# PCB_MASTER_CARRO_MYM.net
KiCad netlist of a schematic drawn in EAGLE
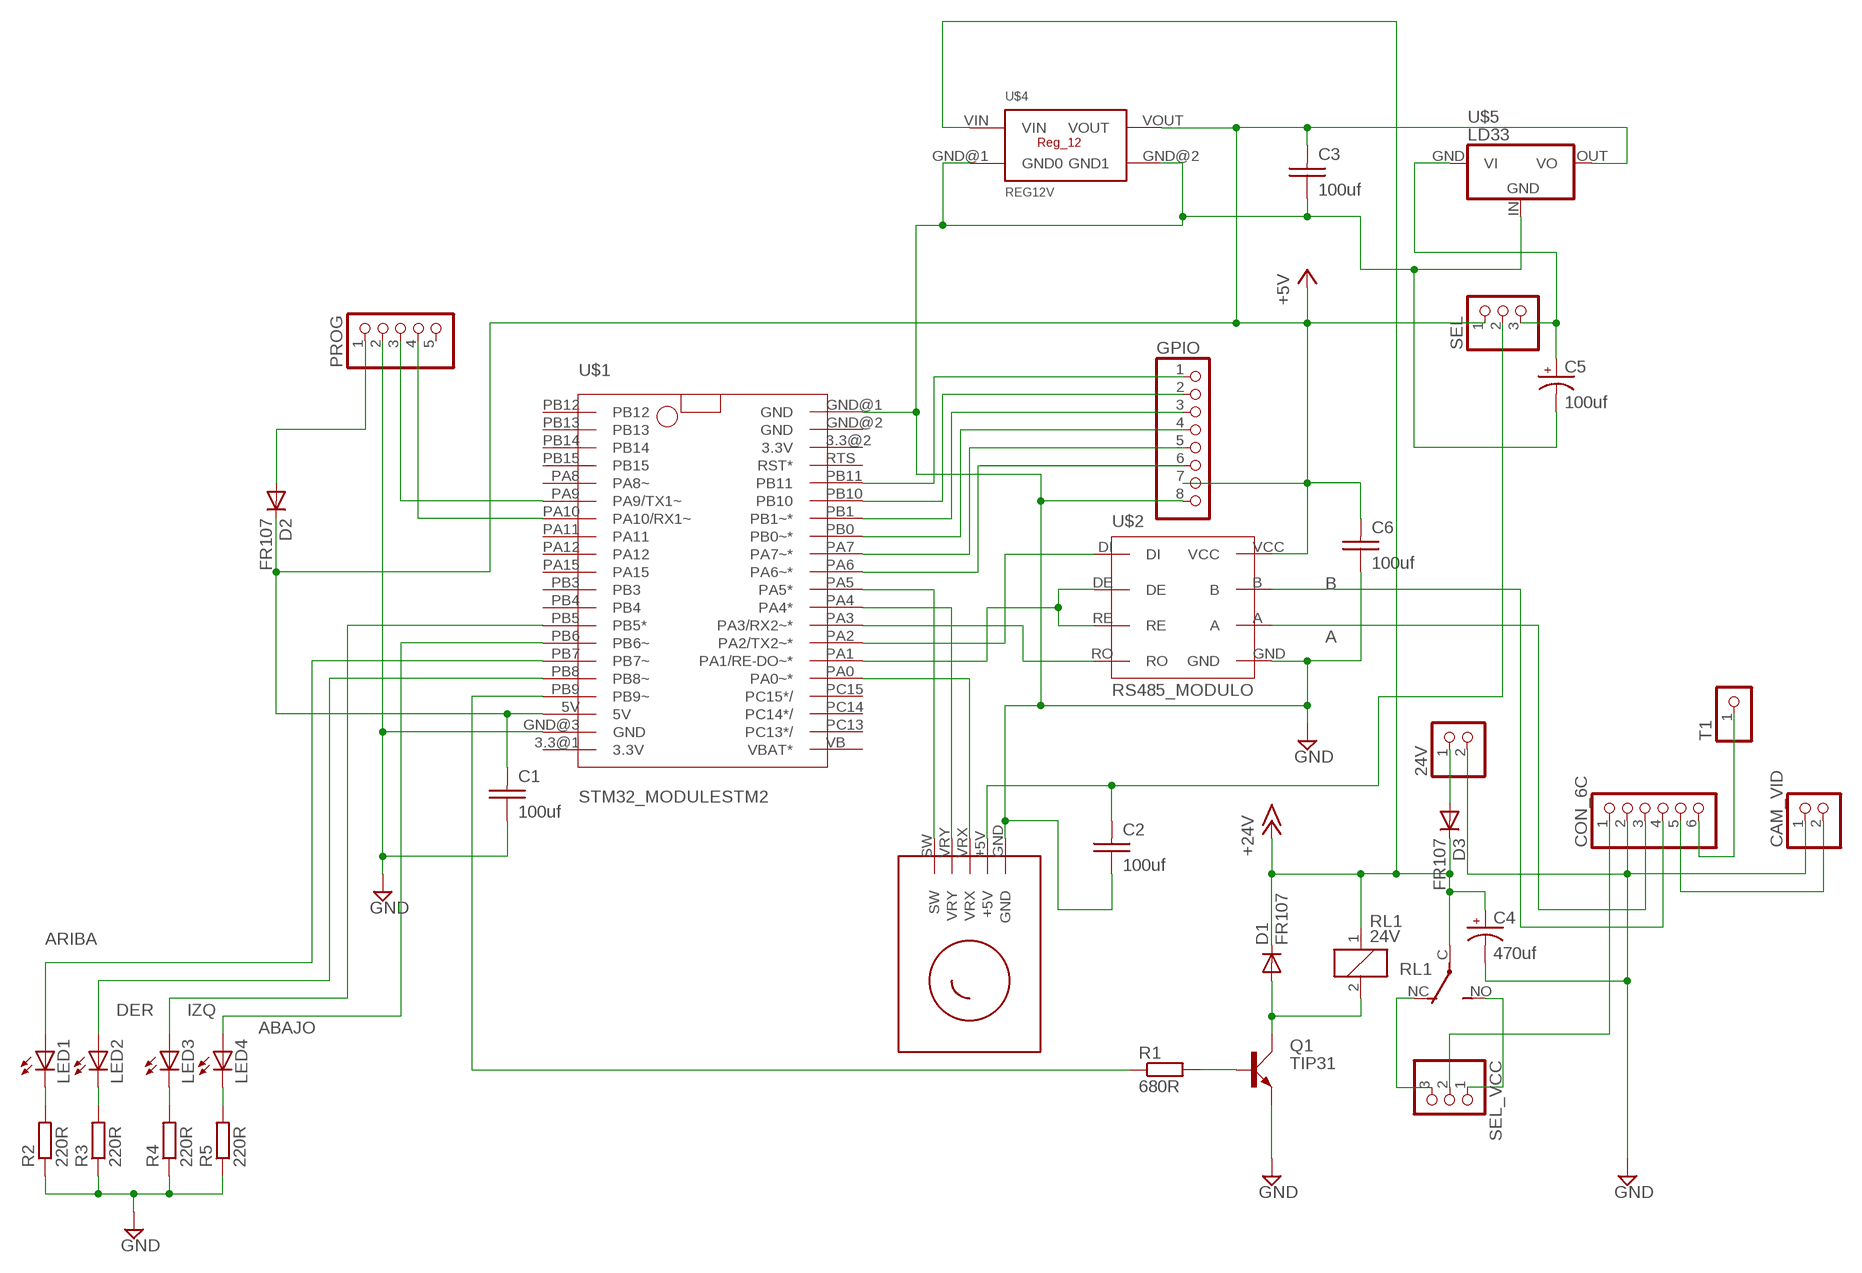
[diagram p0: schematic, sheet 1]

(export (version "E")
  (design (tool "Eeschema 10.0.6"))
  (components
    (comp (ref "24V")
      (value "PINHD-1X2")
      (footprint "eagle-import:1X02")
      (libsource (lib "eagle-import") (part "PINHD-1X2"))
    )
    (comp (ref "C1")
      (value "100uf")
      (footprint "eagle-import:CAP_CER_2,54-5X5")
      (libsource (lib "eagle-import") (part "CAP_CERAMICO_TH2"))
    )
    (comp (ref "C2")
      (value "100uf")
      (footprint "eagle-import:CAP_CER_2,54-5X5")
      (libsource (lib "eagle-import") (part "CAP_CERAMICO_TH2"))
    )
    (comp (ref "C3")
      (value "100uf")
      (footprint "eagle-import:CAP_CER_2,54-5X5")
      (libsource (lib "eagle-import") (part "CAP_CERAMICO_TH2"))
    )
    (comp (ref "C4")
      (value "470uf")
      (footprint "eagle-import:CAP_T_5-D8,5")
      (libsource (lib "eagle-import") (part "CAP_POLARIZADOCAP_T5-8,5"))
    )
    (comp (ref "C5")
      (value "100uf")
      (footprint "eagle-import:CAP_T_3,5-D8")
      (libsource (lib "eagle-import") (part "CAP_POLARIZADOCAP_T3,5-D8"))
    )
    (comp (ref "C6")
      (value "100uf")
      (footprint "eagle-import:CAP_CER_2,54-5X5")
      (libsource (lib "eagle-import") (part "CAP_CERAMICO_TH2"))
    )
    (comp (ref "CAM_VID")
      (value "PINHD-1X2")
      (footprint "eagle-import:1X02")
      (libsource (lib "eagle-import") (part "PINHD-1X2"))
    )
    (comp (ref "CON_6C")
      (value "PINHD-1X6")
      (footprint "eagle-import:1X06")
      (libsource (lib "eagle-import") (part "PINHD-1X6"))
    )
    (comp (ref "D1")
      (value "FR107")
      (footprint "eagle-import:D-5")
      (libsource (lib "eagle-import") (part "DIODOT_5"))
    )
    (comp (ref "D2")
      (value "FR107")
      (footprint "eagle-import:DIODO4MM")
      (libsource (lib "eagle-import") (part "DIODO"))
    )
    (comp (ref "D3")
      (value "FR107")
      (footprint "eagle-import:DIODO4MM")
      (libsource (lib "eagle-import") (part "DIODO"))
    )
    (comp (ref "GPIO")
      (value "PINHD-1X8")
      (footprint "eagle-import:1X08")
      (libsource (lib "eagle-import") (part "PINHD-1X8"))
    )
    (comp (ref "LED1")
      (value "LEDLED_T_3MM")
      (footprint "eagle-import:LED3MM")
      (libsource (lib "eagle-import") (part "LEDLED_T_3MM"))
    )
    (comp (ref "LED2")
      (value "LEDLED_T_3MM")
      (footprint "eagle-import:LED3MM")
      (libsource (lib "eagle-import") (part "LEDLED_T_3MM"))
    )
    (comp (ref "LED3")
      (value "LEDLED_T_3MM")
      (footprint "eagle-import:LED3MM")
      (libsource (lib "eagle-import") (part "LEDLED_T_3MM"))
    )
    (comp (ref "LED4")
      (value "LEDLED_T_3MM")
      (footprint "eagle-import:LED3MM")
      (libsource (lib "eagle-import") (part "LEDLED_T_3MM"))
    )
    (comp (ref "PROG")
      (value "PINHD-1X5")
      (footprint "eagle-import:1X05")
      (libsource (lib "eagle-import") (part "PINHD-1X5"))
    )
    (comp (ref "Q1")
      (value "TIP31")
      (footprint "eagle-import:TO220")
      (libsource (lib "eagle-import") (part "TIP48_TH"))
    )
    (comp (ref "R1")
      (value "680R")
      (footprint "eagle-import:0204_5")
      (libsource (lib "eagle-import") (part "RESISTORT_LARGO"))
    )
    (comp (ref "R2")
      (value "220R")
      (footprint "eagle-import:0204_5")
      (libsource (lib "eagle-import") (part "RESISTORT_LARGO"))
    )
    (comp (ref "R3")
      (value "220R")
      (footprint "eagle-import:0204_5")
      (libsource (lib "eagle-import") (part "RESISTORT_LARGO"))
    )
    (comp (ref "R4")
      (value "220R")
      (footprint "eagle-import:0204_5")
      (libsource (lib "eagle-import") (part "RESISTORT_LARGO"))
    )
    (comp (ref "R5")
      (value "220R")
      (footprint "eagle-import:0204_5")
      (libsource (lib "eagle-import") (part "RESISTORT_LARGO"))
    )
    (comp (ref "RL1")
      (value "24V")
      (footprint "eagle-import:CQ1")
      (libsource (lib "eagle-import") (part "CQ1-12V"))
    )
    (comp (ref "SEL")
      (value "PINHD-1X3")
      (footprint "eagle-import:1X03")
      (libsource (lib "eagle-import") (part "PINHD-1X3"))
    )
    (comp (ref "SEL_VCC")
      (value "PINHD-1X3")
      (footprint "eagle-import:1X03")
      (libsource (lib "eagle-import") (part "PINHD-1X3"))
    )
    (comp (ref "T1")
      (value "PINHD-1X1")
      (footprint "eagle-import:1X01")
      (libsource (lib "eagle-import") (part "PINHD-1X1"))
    )
    (comp (ref "U$1")
      (value "STM32_MODULESTM2")
      (footprint "eagle-import:STM_32MOD")
      (libsource (lib "eagle-import") (part "STM32_MODULESTM2"))
    )
    (comp (ref "U$2")
      (value "RS485_MODULO")
      (footprint "eagle-import:RS485_FP")
      (libsource (lib "eagle-import") (part "RS485_MODULO"))
    )
    (comp (ref "U$3")
      (value "JOYSTICK")
      (footprint "eagle-import:JOYSTICK")
      (libsource (lib "eagle-import") (part "JOYSTICK"))
    )
    (comp (ref "U$4")
      (value "REG12V")
      (footprint "eagle-import:REG12V")
      (libsource (lib "eagle-import") (part "REG12V"))
    )
    (comp (ref "U$5")
      (value "LD33")
      (footprint "eagle-import:78XXS")
      (libsource (lib "eagle-import") (part "LD33"))
    )
  )
  (nets
    (net (code "1") (name "+5V") (class "Default")
      (node (ref "C1") (pin "1") (pinfunction "1_1") (pintype "passive"))
      (node (ref "C3") (pin "1") (pinfunction "1_1") (pintype "passive"))
      (node (ref "C6") (pin "1") (pinfunction "1_1") (pintype "passive"))
      (node (ref "D2") (pin "C") (pinfunction "C_C") (pintype "passive"))
      (node (ref "GPIO") (pin "7") (pinfunction "7_7") (pintype "passive"))
      (node (ref "SEL") (pin "1") (pinfunction "1_1") (pintype "passive"))
      (node (ref "U$1") (pin "5V") (pinfunction "5V_5V") (pintype "bidirectional"))
      (node (ref "U$2") (pin "VCC") (pinfunction "VCC_VCC") (pintype "bidirectional"))
      (node (ref "U$4") (pin "VOUT") (pinfunction "VOUT_VOUT") (pintype "bidirectional"))
      (node (ref "U$5") (pin "OUT") (pinfunction "VO_OUT") (pintype "passive"))
    )
    (net (code "2") (name "+24V") (class "Default")
      (node (ref "C4") (pin "+") (pinfunction "+_+") (pintype "passive"))
      (node (ref "D1") (pin "C") (pinfunction "C_C") (pintype "passive"))
      (node (ref "D3") (pin "C") (pinfunction "C_C") (pintype "passive"))
      (node (ref "RL1") (pin "1") (pinfunction "1_1") (pintype "passive"))
      (node (ref "RL1") (pin "C") (pinfunction "P_C") (pintype "passive"))
      (node (ref "U$4") (pin "VIN") (pinfunction "VIN_VIN") (pintype "bidirectional"))
    )
    (net (code "3") (name "/A") (class "Default")
      (node (ref "CON_6C") (pin "3") (pinfunction "3_3") (pintype "passive"))
      (node (ref "U$2") (pin "A") (pinfunction "A_A") (pintype "bidirectional"))
    )
    (net (code "4") (name "/ABAJO") (class "Default")
      (node (ref "LED4") (pin "A") (pinfunction "A_A") (pintype "passive"))
      (node (ref "U$1") (pin "PB6") (pinfunction "PB6~{}_PB6") (pintype "bidirectional"))
    )
    (net (code "5") (name "/ARIBA") (class "Default")
      (node (ref "LED1") (pin "A") (pinfunction "A_A") (pintype "passive"))
      (node (ref "U$1") (pin "PB7") (pinfunction "PB7~{}_PB7") (pintype "bidirectional"))
    )
    (net (code "6") (name "/B") (class "Default")
      (node (ref "CON_6C") (pin "4") (pinfunction "4_4") (pintype "passive"))
      (node (ref "U$2") (pin "B") (pinfunction "B_B") (pintype "bidirectional"))
    )
    (net (code "7") (name "/DER") (class "Default")
      (node (ref "LED2") (pin "A") (pinfunction "A_A") (pintype "passive"))
      (node (ref "U$1") (pin "PB8") (pinfunction "PB8~{}_PB8") (pintype "bidirectional"))
    )
    (net (code "8") (name "/IZQ") (class "Default")
      (node (ref "LED3") (pin "A") (pinfunction "A_A") (pintype "passive"))
      (node (ref "U$1") (pin "PB5") (pinfunction "PB5*_PB5") (pintype "bidirectional"))
    )
    (net (code "9") (name "GND") (class "Default")
      (node (ref "24V") (pin "2") (pinfunction "2_2") (pintype "passive"))
      (node (ref "C1") (pin "2") (pinfunction "2_2") (pintype "passive"))
      (node (ref "C2") (pin "2") (pinfunction "2_2") (pintype "passive"))
      (node (ref "C3") (pin "2") (pinfunction "2_2") (pintype "passive"))
      (node (ref "C4") (pin "-") (pinfunction "-_-") (pintype "passive"))
      (node (ref "C5") (pin "-") (pinfunction "-_-") (pintype "passive"))
      (node (ref "C6") (pin "2") (pinfunction "2_2") (pintype "passive"))
      (node (ref "CAM_VID") (pin "1") (pinfunction "1_1") (pintype "passive"))
      (node (ref "CON_6C") (pin "2") (pinfunction "2_2") (pintype "passive"))
      (node (ref "GPIO") (pin "8") (pinfunction "8_8") (pintype "passive"))
      (node (ref "PROG") (pin "2") (pinfunction "2_2") (pintype "passive"))
      (node (ref "Q1") (pin "E") (pinfunction "E_E") (pintype "passive"))
      (node (ref "R2") (pin "1") (pinfunction "1_1") (pintype "passive"))
      (node (ref "R3") (pin "1") (pinfunction "1_1") (pintype "passive"))
      (node (ref "R4") (pin "1") (pinfunction "1_1") (pintype "passive"))
      (node (ref "R5") (pin "1") (pinfunction "1_1") (pintype "passive"))
      (node (ref "U$1") (pin "GND@1") (pinfunction "GND_GND@1") (pintype "bidirectional"))
      (node (ref "U$1") (pin "GND@3") (pinfunction "GND_GND@3") (pintype "bidirectional"))
      (node (ref "U$2") (pin "GND") (pinfunction "GND_GND") (pintype "bidirectional"))
      (node (ref "U$3") (pin "GND") (pinfunction "GND_GND") (pintype "bidirectional"))
      (node (ref "U$4") (pin "GND@1") (pinfunction "GND0_GND@1") (pintype "bidirectional"))
      (node (ref "U$4") (pin "GND@2") (pinfunction "GND1_GND@2") (pintype "bidirectional"))
      (node (ref "U$5") (pin "IN") (pinfunction "GND_IN") (pintype "passive"))
    )
    (net (code "10") (name "Net-(24V-Pad1)") (class "Default")
      (node (ref "24V") (pin "1") (pinfunction "1_1") (pintype "passive"))
      (node (ref "D3") (pin "A") (pinfunction "A_A") (pintype "passive"))
    )
    (net (code "11") (name "Net-(C2-Pad1)") (class "Default")
      (node (ref "C2") (pin "1") (pinfunction "1_1") (pintype "passive"))
      (node (ref "SEL") (pin "2") (pinfunction "2_2") (pintype "passive"))
      (node (ref "U$3") (pin "+5V") (pinfunction "+5V_+5V") (pintype "bidirectional"))
    )
    (net (code "12") (name "Net-(CAM_VID-Pad2)") (class "Default")
      (node (ref "CAM_VID") (pin "2") (pinfunction "2_2") (pintype "passive"))
      (node (ref "CON_6C") (pin "5") (pinfunction "5_5") (pintype "passive"))
    )
    (net (code "13") (name "Net-(CON_6C-Pad1)") (class "Default")
      (node (ref "CON_6C") (pin "1") (pinfunction "1_1") (pintype "passive"))
      (node (ref "SEL_VCC") (pin "2") (pinfunction "2_2") (pintype "passive"))
    )
    (net (code "14") (name "Net-(CON_6C-Pad6)") (class "Default")
      (node (ref "CON_6C") (pin "6") (pinfunction "6_6") (pintype "passive"))
      (node (ref "T1") (pin "1") (pinfunction "1_1") (pintype "passive"))
    )
    (net (code "15") (name "Net-(D1-PadA)") (class "Default")
      (node (ref "D1") (pin "A") (pinfunction "A_A") (pintype "passive"))
      (node (ref "Q1") (pin "C") (pinfunction "C_C") (pintype "passive"))
      (node (ref "RL1") (pin "2") (pinfunction "2_2") (pintype "passive"))
    )
    (net (code "16") (name "Net-(D2-PadA)") (class "Default")
      (node (ref "D2") (pin "A") (pinfunction "A_A") (pintype "passive"))
      (node (ref "PROG") (pin "1") (pinfunction "1_1") (pintype "passive"))
    )
    (net (code "17") (name "Net-(GPIO-Pad1)") (class "Default")
      (node (ref "GPIO") (pin "1") (pinfunction "1_1") (pintype "passive"))
      (node (ref "U$1") (pin "PB11") (pinfunction "PB11_PB11") (pintype "bidirectional"))
    )
    (net (code "18") (name "Net-(GPIO-Pad2)") (class "Default")
      (node (ref "GPIO") (pin "2") (pinfunction "2_2") (pintype "passive"))
      (node (ref "U$1") (pin "PB10") (pinfunction "PB10_PB10") (pintype "bidirectional"))
    )
    (net (code "19") (name "Net-(LED1-C)") (class "Default")
      (node (ref "LED1") (pin "K") (pinfunction "C_K") (pintype "passive"))
      (node (ref "R2") (pin "2") (pinfunction "2_2") (pintype "passive"))
    )
    (net (code "20") (name "Net-(LED2-C)") (class "Default")
      (node (ref "LED2") (pin "K") (pinfunction "C_K") (pintype "passive"))
      (node (ref "R3") (pin "2") (pinfunction "2_2") (pintype "passive"))
    )
    (net (code "21") (name "Net-(LED3-C)") (class "Default")
      (node (ref "LED3") (pin "K") (pinfunction "C_K") (pintype "passive"))
      (node (ref "R4") (pin "2") (pinfunction "2_2") (pintype "passive"))
    )
    (net (code "22") (name "Net-(LED4-C)") (class "Default")
      (node (ref "LED4") (pin "K") (pinfunction "C_K") (pintype "passive"))
      (node (ref "R5") (pin "2") (pinfunction "2_2") (pintype "passive"))
    )
    (net (code "23") (name "Net-(Q1-PadB)") (class "Default")
      (node (ref "Q1") (pin "B") (pinfunction "B_B") (pintype "passive"))
      (node (ref "R1") (pin "2") (pinfunction "2_2") (pintype "passive"))
    )
    (net (code "24") (name "Net-(RL1B-O)") (class "Default")
      (node (ref "RL1") (pin "NC") (pinfunction "O_NC") (pintype "passive"))
      (node (ref "SEL_VCC") (pin "3") (pinfunction "3_3") (pintype "passive"))
    )
    (net (code "25") (name "Net-(RL1B-S)") (class "Default")
      (node (ref "RL1") (pin "NO") (pinfunction "S_NO") (pintype "passive"))
      (node (ref "SEL_VCC") (pin "1") (pinfunction "1_1") (pintype "passive"))
    )
    (net (code "26") (name "Net-(U$1-PA0~{*})") (class "Default")
      (node (ref "U$1") (pin "PA0") (pinfunction "PA0~{*}_PA0") (pintype "bidirectional"))
      (node (ref "U$3") (pin "VRX") (pinfunction "VRX_VRX") (pintype "bidirectional"))
    )
    (net (code "27") (name "Net-(U$1-PA1{slash}RE-DO~{*})") (class "Default")
      (node (ref "U$1") (pin "PA1") (pinfunction "PA1/RE-DO~{*}_PA1") (pintype "bidirectional"))
      (node (ref "U$2") (pin "DE") (pinfunction "DE_DE") (pintype "bidirectional"))
      (node (ref "U$2") (pin "RE") (pinfunction "RE_RE") (pintype "bidirectional"))
    )
    (net (code "28") (name "Net-(U$1-PA2{slash}TX2~{*})") (class "Default")
      (node (ref "U$1") (pin "PA2") (pinfunction "PA2/TX2~{*}_PA2") (pintype "bidirectional"))
      (node (ref "U$2") (pin "DI") (pinfunction "DI_DI") (pintype "bidirectional"))
    )
    (net (code "29") (name "Net-(U$1-PA3{slash}RX2~{*})") (class "Default")
      (node (ref "U$1") (pin "PA3") (pinfunction "PA3/RX2~{*}_PA3") (pintype "bidirectional"))
      (node (ref "U$2") (pin "RO") (pinfunction "RO_RO") (pintype "bidirectional"))
    )
    (net (code "30") (name "Net-(U$1-PA4*)") (class "Default")
      (node (ref "U$1") (pin "PA4") (pinfunction "PA4*_PA4") (pintype "bidirectional"))
      (node (ref "U$3") (pin "VRY") (pinfunction "VRY_VRY") (pintype "bidirectional"))
    )
    (net (code "31") (name "Net-(U$1-PA5*)") (class "Default")
      (node (ref "U$1") (pin "PA5") (pinfunction "PA5*_PA5") (pintype "bidirectional"))
      (node (ref "U$3") (pin "SW") (pinfunction "SW_SW") (pintype "bidirectional"))
    )
    (net (code "32") (name "Net-(U$1-PA6~{*})") (class "Default")
      (node (ref "GPIO") (pin "6") (pinfunction "6_6") (pintype "passive"))
      (node (ref "U$1") (pin "PA6") (pinfunction "PA6~{*}_PA6") (pintype "bidirectional"))
    )
    (net (code "33") (name "Net-(U$1-PA7~{*})") (class "Default")
      (node (ref "GPIO") (pin "5") (pinfunction "5_5") (pintype "passive"))
      (node (ref "U$1") (pin "PA7") (pinfunction "PA7~{*}_PA7") (pintype "bidirectional"))
    )
    (net (code "34") (name "Net-(U$1-PA9{slash}TX1~{})") (class "Default")
      (node (ref "PROG") (pin "3") (pinfunction "3_3") (pintype "passive"))
      (node (ref "U$1") (pin "PA9") (pinfunction "PA9/TX1~{}_PA9") (pintype "bidirectional"))
    )
    (net (code "35") (name "Net-(U$1-PA10{slash}RX1~{})") (class "Default")
      (node (ref "PROG") (pin "4") (pinfunction "4_4") (pintype "passive"))
      (node (ref "U$1") (pin "PA10") (pinfunction "PA10/RX1~{}_PA10") (pintype "bidirectional"))
    )
    (net (code "36") (name "Net-(U$1-PB0~{*})") (class "Default")
      (node (ref "GPIO") (pin "4") (pinfunction "4_4") (pintype "passive"))
      (node (ref "U$1") (pin "PB0") (pinfunction "PB0~{*}_PB0") (pintype "bidirectional"))
    )
    (net (code "37") (name "Net-(U$1-PB1~{*})") (class "Default")
      (node (ref "GPIO") (pin "3") (pinfunction "3_3") (pintype "passive"))
      (node (ref "U$1") (pin "PB1") (pinfunction "PB1~{*}_PB1") (pintype "bidirectional"))
    )
    (net (code "38") (name "Net-(U$1-PB9~{})") (class "Default")
      (node (ref "R1") (pin "1") (pinfunction "1_1") (pintype "passive"))
      (node (ref "U$1") (pin "PB9") (pinfunction "PB9~{}_PB9") (pintype "bidirectional"))
    )
    (net (code "39") (name "Net-(U$5-VI)") (class "Default")
      (node (ref "C5") (pin "+") (pinfunction "+_+") (pintype "passive"))
      (node (ref "SEL") (pin "3") (pinfunction "3_3") (pintype "passive"))
      (node (ref "U$5") (pin "GND") (pinfunction "VI_GND") (pintype "input"))
    )
    (net (code "40") (name "unconnected-(PROG-Pad5)") (class "Default")
      (node (ref "PROG") (pin "5") (pinfunction "5_5") (pintype "passive"))
    )
    (net (code "41") (name "unconnected-(U$1-3.3V-Pad3.3@1)") (class "Default")
      (node (ref "U$1") (pin "3.3@1") (pinfunction "3.3V_3.3@1") (pintype "bidirectional"))
    )
    (net (code "42") (name "unconnected-(U$1-3.3V-Pad3.3@2)") (class "Default")
      (node (ref "U$1") (pin "3.3@2") (pinfunction "3.3V_3.3@2") (pintype "bidirectional"))
    )
    (net (code "43") (name "unconnected-(U$1-GND-PadGND@2)") (class "Default")
      (node (ref "U$1") (pin "GND@2") (pinfunction "GND_GND@2") (pintype "bidirectional"))
    )
    (net (code "44") (name "unconnected-(U$1-PA8~{}-PadPA8)") (class "Default")
      (node (ref "U$1") (pin "PA8") (pinfunction "PA8~{}_PA8") (pintype "bidirectional"))
    )
    (net (code "45") (name "unconnected-(U$1-PC13*{slash}-PadPC13)") (class "Default")
      (node (ref "U$1") (pin "PC13") (pinfunction "PC13*/_PC13") (pintype "bidirectional"))
    )
    (net (code "46") (name "unconnected-(U$1-PC14*{slash}-PadPC14)") (class "Default")
      (node (ref "U$1") (pin "PC14") (pinfunction "PC14*/_PC14") (pintype "bidirectional"))
    )
    (net (code "47") (name "unconnected-(U$1-PC15*{slash}-PadPC15)") (class "Default")
      (node (ref "U$1") (pin "PC15") (pinfunction "PC15*/_PC15") (pintype "bidirectional"))
    )
    (net (code "48") (name "unconnected-(U$1-PadPA11)") (class "Default")
      (node (ref "U$1") (pin "PA11") (pinfunction "PA11_PA11") (pintype "bidirectional"))
    )
    (net (code "49") (name "unconnected-(U$1-PadPA12)") (class "Default")
      (node (ref "U$1") (pin "PA12") (pinfunction "PA12_PA12") (pintype "bidirectional"))
    )
    (net (code "50") (name "unconnected-(U$1-PadPA15)") (class "Default")
      (node (ref "U$1") (pin "PA15") (pinfunction "PA15_PA15") (pintype "bidirectional"))
    )
    (net (code "51") (name "unconnected-(U$1-PadPB3)") (class "Default")
      (node (ref "U$1") (pin "PB3") (pinfunction "PB3_PB3") (pintype "bidirectional"))
    )
    (net (code "52") (name "unconnected-(U$1-PadPB4)") (class "Default")
      (node (ref "U$1") (pin "PB4") (pinfunction "PB4_PB4") (pintype "bidirectional"))
    )
    (net (code "53") (name "unconnected-(U$1-PadPB12)") (class "Default")
      (node (ref "U$1") (pin "PB12") (pinfunction "PB12_PB12") (pintype "bidirectional"))
    )
    (net (code "54") (name "unconnected-(U$1-PadPB13)") (class "Default")
      (node (ref "U$1") (pin "PB13") (pinfunction "PB13_PB13") (pintype "bidirectional"))
    )
    (net (code "55") (name "unconnected-(U$1-PadPB14)") (class "Default")
      (node (ref "U$1") (pin "PB14") (pinfunction "PB14_PB14") (pintype "bidirectional"))
    )
    (net (code "56") (name "unconnected-(U$1-PadPB15)") (class "Default")
      (node (ref "U$1") (pin "PB15") (pinfunction "PB15_PB15") (pintype "bidirectional"))
    )
    (net (code "57") (name "unconnected-(U$1-RST*-PadRTS)") (class "Default")
      (node (ref "U$1") (pin "RTS") (pinfunction "RST*_RTS") (pintype "bidirectional"))
    )
    (net (code "58") (name "unconnected-(U$1-VBAT*-PadVB)") (class "Default")
      (node (ref "U$1") (pin "VB") (pinfunction "VBAT*_VB") (pintype "bidirectional"))
    )
  )
)
